# MotorController.net
KiCad netlist of a schematic drawn in Altium Designer
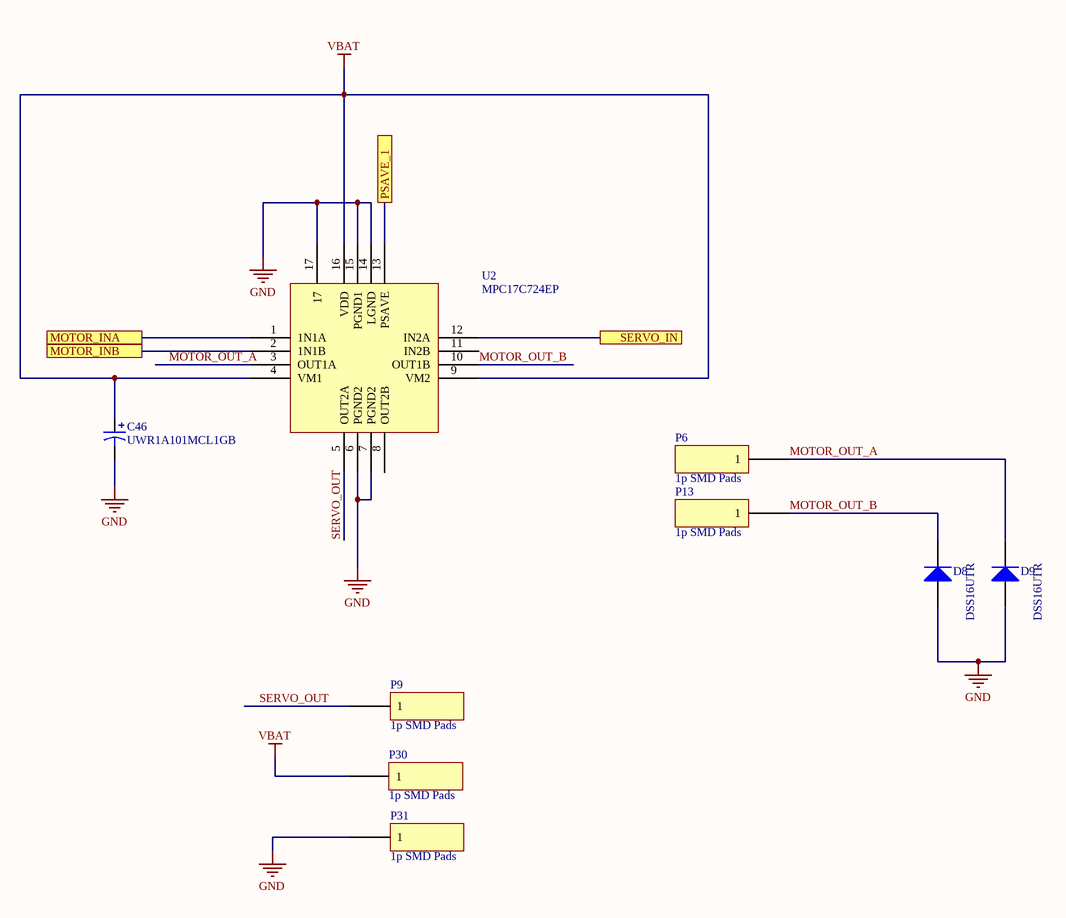
[diagram p0: MotorController.SchDoc]

(export (version "E")
  (design (tool "Eeschema 10.0.6"))
  (components
    (comp (ref "C46")
      (value "UWR1A101MCL1GB")
      (footprint "UWR1A101MCL1GB")
      (description "100uF Electrolytic")
      (libsource (lib "parts") (part "UWR1A101MCL1GB"))
    )
    (comp (ref "D8")
      (value "DSS16UTR")
      (footprint "MCC-SOD-123FL_V")
      (description "SCHOTTKY 60V SOD-123FL")
      (fields (field (name "MANUFACTURER") "Micro Commercial Components"))
      (libsource (lib "Altium Content Vault") (part "D-AK-2"))
    )
    (comp (ref "D9")
      (value "DSS16UTR")
      (footprint "MCC-SOD-123FL_V")
      (description "SCHOTTKY 60V SOD-123FL Reel")
      (fields (field (name "MANUFACTURER") "Micro Commercial Components"))
      (libsource (lib "Altium Content Vault") (part "D-AK-2"))
    )
    (comp (ref "P6") (value "1p SMD Pads") (footprint "1p SMD pad") (libsource (lib "") (part "1p SMD_1")))
    (comp (ref "P9") (value "1p SMD Pads") (footprint "1p SMD pad") (libsource (lib "parts") (part "1p SMD")))
    (comp (ref "P13") (value "1p SMD Pads") (footprint "1p SMD pad") (libsource (lib "") (part "1p SMD_1")))
    (comp (ref "P30")
      (value "1p SMD Pads")
      (footprint "1p SMD pad")
      (libsource (lib "parts") (part "1p SMD"))
    )
    (comp (ref "P31")
      (value "1p SMD Pads")
      (footprint "1p SMD pad")
      (libsource (lib "parts") (part "1p SMD"))
    )
    (comp (ref "U2")
      (value "MPC17C724EP")
      (footprint "QFN50P300X300X85_HS-17N")
      (description "0.4 A Dual H-Bridge Motor Driver")
      (libsource (lib "parts") (part "MPC17C724EP"))
    )
  )
  (nets
    (net (code "1") (name "/MOTOR_INA") (class "Default")
      (node (ref "U2") (pin "1") (pinfunction "1N1A_1") (pintype "passive"))
    )
    (net (code "2") (name "/MOTOR_INB") (class "Default")
      (node (ref "U2") (pin "2") (pinfunction "1N1B_2") (pintype "passive"))
    )
    (net (code "3") (name "/MOTOR_OUT_A") (class "Default")
      (node (ref "D9") (pin "2") (pinfunction "K_2") (pintype "passive"))
      (node (ref "P6") (pin "1") (pinfunction "1_1") (pintype "passive"))
      (node (ref "U2") (pin "3") (pinfunction "OUT1A_3") (pintype "passive"))
    )
    (net (code "4") (name "/MOTOR_OUT_B") (class "Default")
      (node (ref "D8") (pin "2") (pinfunction "K_2") (pintype "passive"))
      (node (ref "P13") (pin "1") (pinfunction "1_1") (pintype "passive"))
      (node (ref "U2") (pin "10") (pinfunction "OUT1B_10") (pintype "passive"))
    )
    (net (code "5") (name "/PSAVE_1") (class "Default")
      (node (ref "U2") (pin "13") (pinfunction "PSAVE_13") (pintype "passive"))
    )
    (net (code "6") (name "/SERVO_IN") (class "Default")
      (node (ref "U2") (pin "12") (pinfunction "IN2A_12") (pintype "passive"))
    )
    (net (code "7") (name "/SERVO_OUT") (class "Default")
      (node (ref "P9") (pin "1") (pinfunction "1_1") (pintype "passive"))
      (node (ref "U2") (pin "5") (pinfunction "OUT2A_5") (pintype "passive"))
    )
    (net (code "8") (name "GND") (class "Default")
      (node (ref "C46") (pin "2") (pinfunction "2_2") (pintype "passive"))
      (node (ref "D8") (pin "1") (pinfunction "A_1") (pintype "passive"))
      (node (ref "D9") (pin "1") (pinfunction "A_1") (pintype "passive"))
      (node (ref "P31") (pin "1") (pinfunction "1_1") (pintype "passive"))
      (node (ref "U2") (pin "14") (pinfunction "LGND_14") (pintype "passive"))
      (node (ref "U2") (pin "15") (pinfunction "PGND1_15") (pintype "passive"))
      (node (ref "U2") (pin "17") (pinfunction "17_17") (pintype "passive"))
      (node (ref "U2") (pin "6") (pinfunction "PGND2_6") (pintype "passive"))
      (node (ref "U2") (pin "7") (pinfunction "PGND2_7") (pintype "passive"))
    )
    (net (code "9") (name "VBAT") (class "Default")
      (node (ref "C46") (pin "1") (pinfunction "1_1") (pintype "passive"))
      (node (ref "P30") (pin "1") (pinfunction "1_1") (pintype "passive"))
      (node (ref "U2") (pin "16") (pinfunction "VDD_16") (pintype "passive"))
      (node (ref "U2") (pin "4") (pinfunction "VM1_4") (pintype "passive"))
      (node (ref "U2") (pin "9") (pinfunction "VM2_9") (pintype "passive"))
    )
    (net (code "10") (name "unconnected-(U2-IN2B-Pad11)") (class "Default")
      (node (ref "U2") (pin "11") (pinfunction "IN2B_11") (pintype "passive"))
    )
    (net (code "11") (name "unconnected-(U2-OUT2B-Pad8)") (class "Default")
      (node (ref "U2") (pin "8") (pinfunction "OUT2B_8") (pintype "passive"))
    )
  )
)
